# fpga.net
KiCad netlist of a schematic drawn in Altium Designer
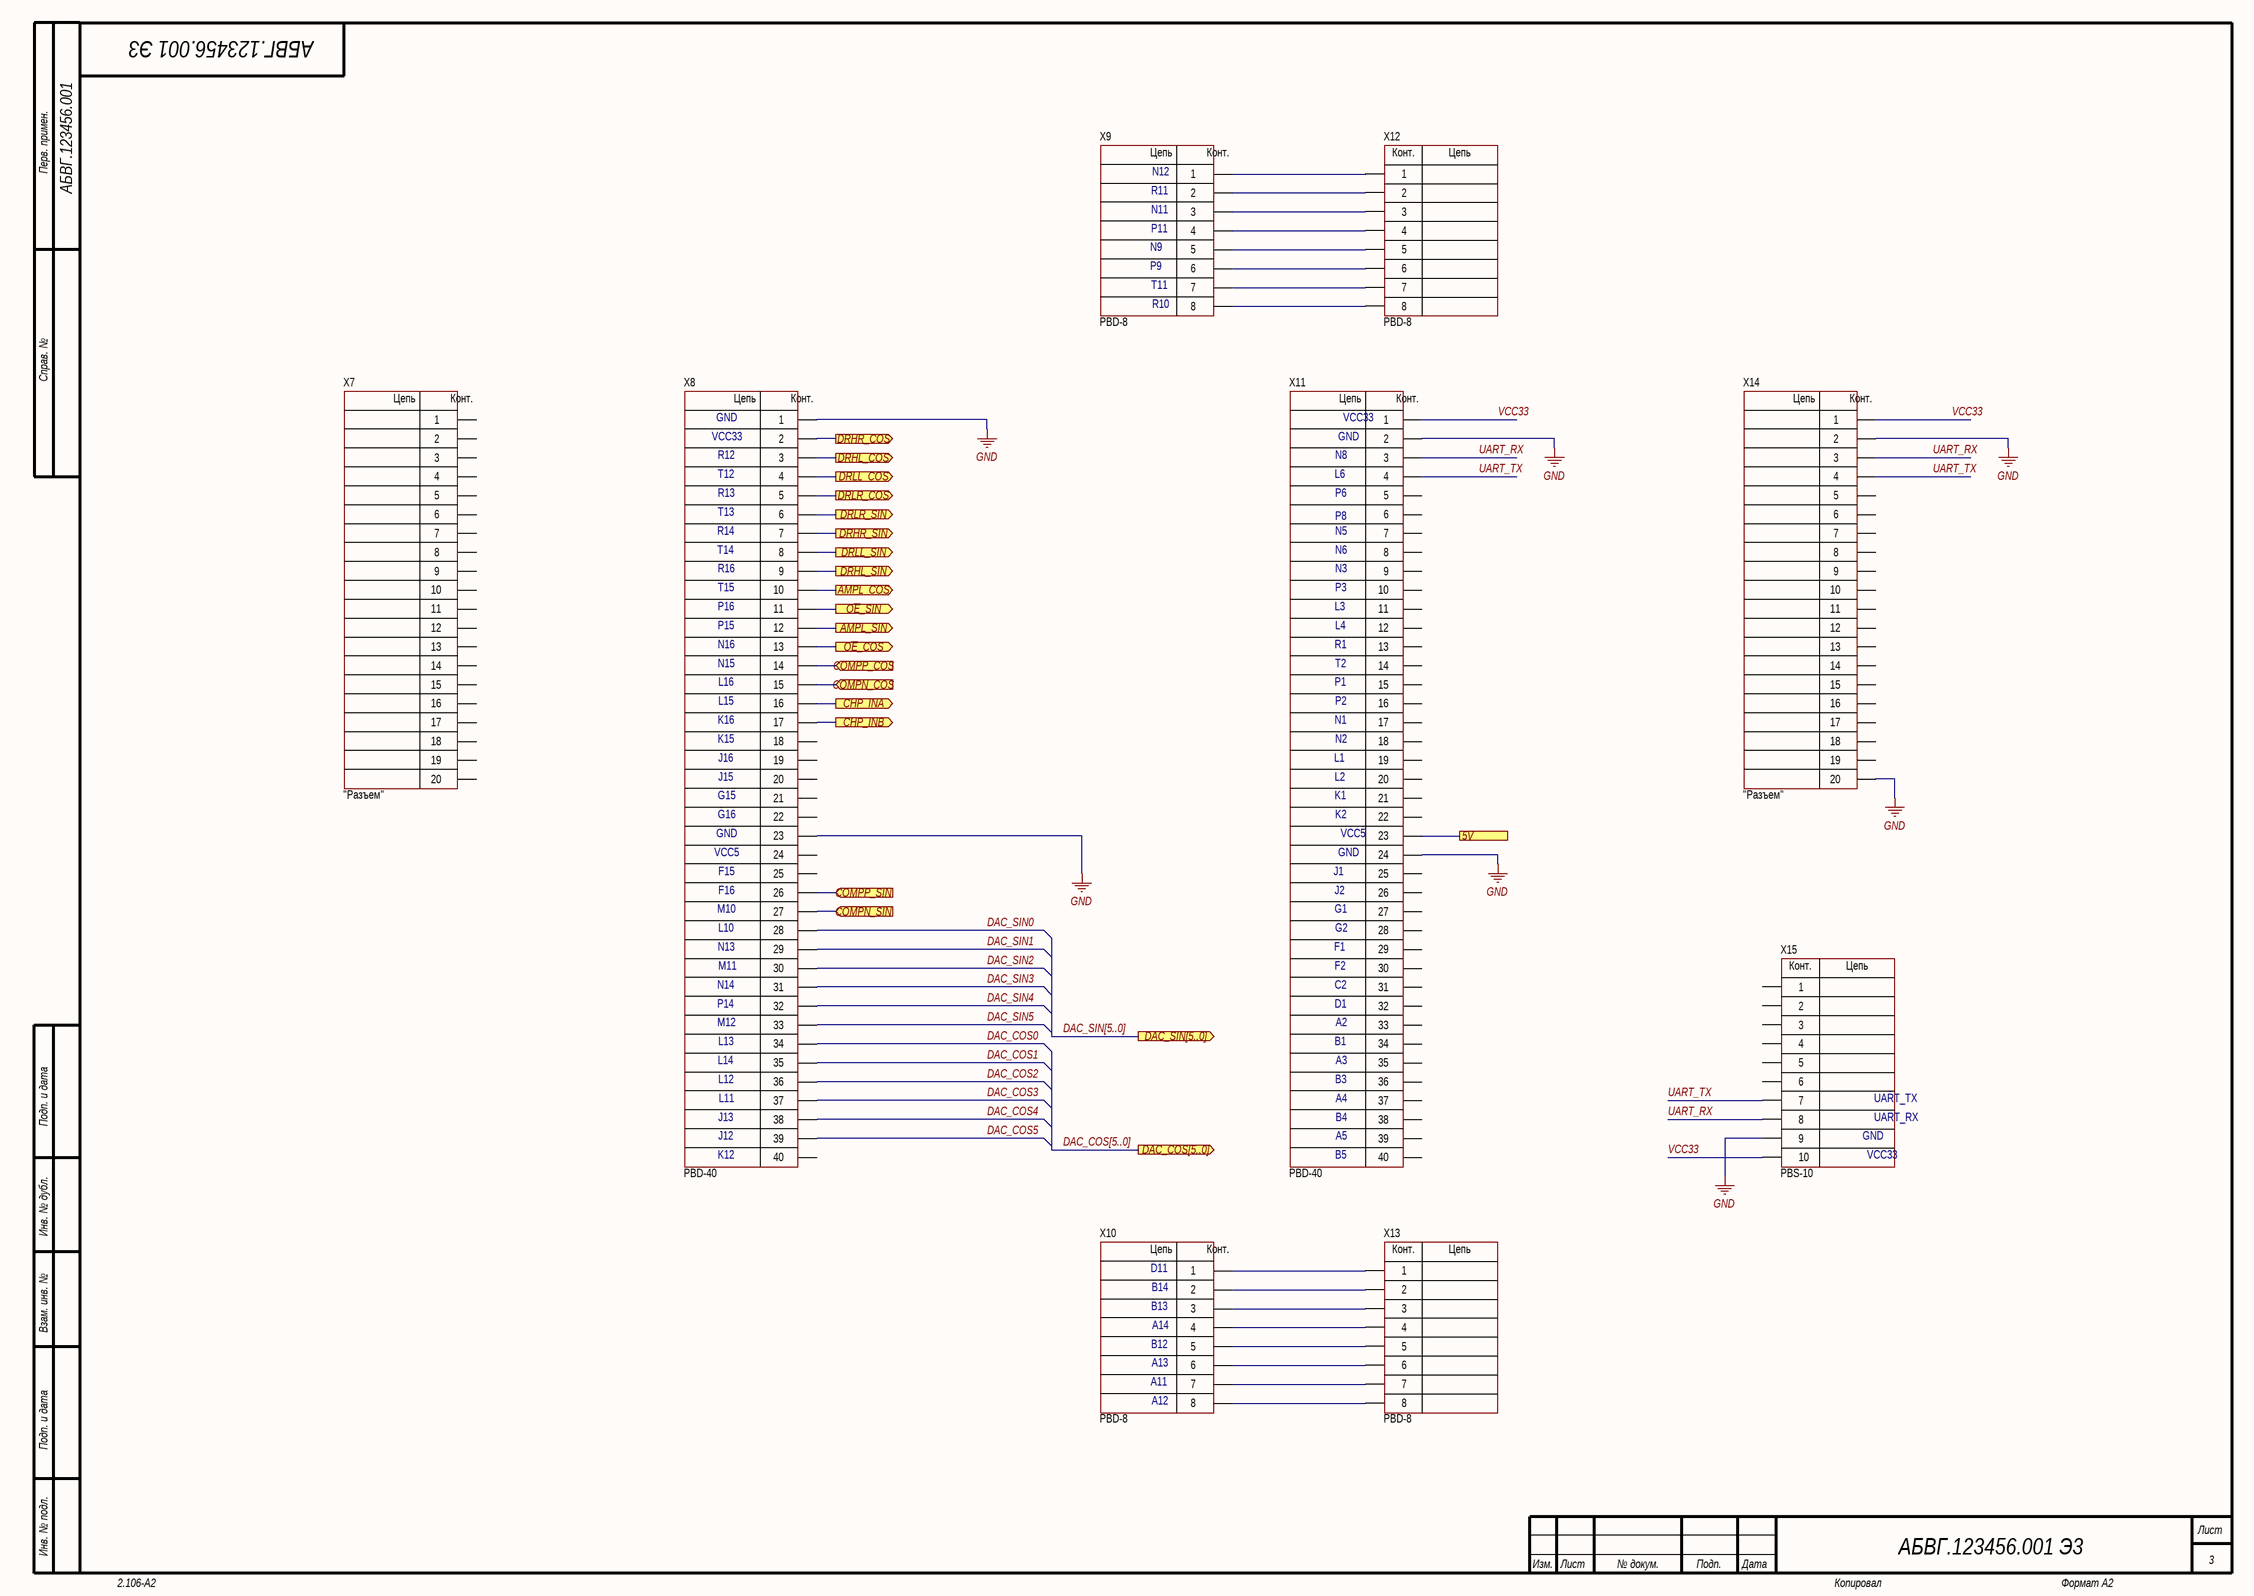
[diagram p0: fpga.SchDoc]

(export (version "E")
  (design (tool "Eeschema 10.0.6"))
  (components
    (comp (ref "X7")
      (value "~")
      (footprint "CON: PBD-20")
      (fields
        (field (name "MANUFACTURER") "Connfly")
        (field (name "VALUEMANUFACTURERPARTNUMBER") "Connector, 20pin, 2.54mm, 500VAC, 3A")
        (field (name "PARTNUMBER") "PBD-20")
        (field (name "COMMENTTEXT") "\"Разъем\"")
      )
      (libsource (lib "connector") (part "PBD-20"))
    )
    (comp (ref "X8")
      (value "~")
      (footprint "CON: PBD-40 (2.00)")
      (fields
        (field (name "MANUFACTURER") "Connfly")
        (field (name "VALUEMANUFACTURERPARTNUMBER") "Connector, 20pin, 2.54mm, 500VAC, 3A")
        (field (name "PARTNUMBER") "PBD-40")
      )
      (libsource (lib "connector") (part "PBD-40"))
    )
    (comp (ref "X9")
      (value "~")
      (footprint "CON: PBD2-8 (2.00)")
      (fields
        (field (name "MANUFACTURER") "Connfly")
        (field (name "VALUEMANUFACTURERPARTNUMBER") "Connector, 8pin, 2.54mm, 500VAC, 3A")
        (field (name "PARTNUMBER") "PBD-8")
      )
      (libsource (lib "connector") (part "PBD-8"))
    )
    (comp (ref "X10")
      (value "~")
      (footprint "CON: PBD2-8 (2.00)")
      (fields
        (field (name "MANUFACTURER") "Connfly")
        (field (name "VALUEMANUFACTURERPARTNUMBER") "Connector, 8pin, 2.54mm, 500VAC, 3A")
        (field (name "PARTNUMBER") "PBD-8")
      )
      (libsource (lib "connector") (part "PBD-8"))
    )
    (comp (ref "X11")
      (value "~")
      (footprint "CON: PBD-40 (2.00)")
      (fields
        (field (name "MANUFACTURER") "Connfly")
        (field (name "VALUEMANUFACTURERPARTNUMBER") "Connector, 20pin, 2.54mm, 500VAC, 3A")
        (field (name "PARTNUMBER") "PBD-40")
      )
      (libsource (lib "connector") (part "PBD-40"))
    )
    (comp (ref "X12")
      (value "~")
      (footprint "CON: PBD-8")
      (fields
        (field (name "MANUFACTURER") "Connfly")
        (field (name "VALUEMANUFACTURERPARTNUMBER") "Connector, 8pin, 2.54mm, 500VAC, 3A")
        (field (name "PARTNUMBER") "PBD-8")
      )
      (libsource (lib "") (part "PBD-8_1"))
    )
    (comp (ref "X13")
      (value "~")
      (footprint "CON: PBD-8")
      (fields
        (field (name "MANUFACTURER") "Connfly")
        (field (name "VALUEMANUFACTURERPARTNUMBER") "Connector, 8pin, 2.54mm, 500VAC, 3A")
        (field (name "PARTNUMBER") "PBD-8")
      )
      (libsource (lib "") (part "PBD-8_1"))
    )
    (comp (ref "X14")
      (value "~")
      (footprint "CON: PBD-20")
      (fields
        (field (name "MANUFACTURER") "Connfly")
        (field (name "VALUEMANUFACTURERPARTNUMBER") "Connector, 20pin, 2.54mm, 500VAC, 3A")
        (field (name "PARTNUMBER") "PBD-20")
        (field (name "COMMENTTEXT") "\"Разъем\"")
      )
      (libsource (lib "connector") (part "PBD-20"))
    )
    (comp (ref "X15")
      (value "~")
      (footprint "CON: PBS-10R")
      (fields
        (field (name "MANUFACTURER") "Connfly")
        (field (name "VALUEMANUFACTURERPARTNUMBER") "Connector, 10pin, 2.54mm, 500VAC, 3A")
        (field (name "PARTNUMBER") "PBS-10")
      )
      (libsource (lib "connector") (part "PBS-10R"))
    )
  )
  (nets
    (net (code "1") (name "/5V") (class "Default")
      (node (ref "X11") (pin "23") (pinfunction "23_23") (pintype "passive"))
    )
    (net (code "2") (name "/AMPL_COS") (class "Default")
      (node (ref "X8") (pin "10") (pinfunction "10_10") (pintype "passive"))
    )
    (net (code "3") (name "/AMPL_SIN") (class "Default")
      (node (ref "X8") (pin "12") (pinfunction "12_12") (pintype "passive"))
    )
    (net (code "4") (name "/CHP_INA") (class "Default")
      (node (ref "X8") (pin "16") (pinfunction "16_16") (pintype "passive"))
    )
    (net (code "5") (name "/CHP_INB") (class "Default")
      (node (ref "X8") (pin "17") (pinfunction "17_17") (pintype "passive"))
    )
    (net (code "6") (name "/COMPN_COS") (class "Default")
      (node (ref "X8") (pin "15") (pinfunction "15_15") (pintype "passive"))
    )
    (net (code "7") (name "/COMPN_SIN") (class "Default")
      (node (ref "X8") (pin "27") (pinfunction "27_27") (pintype "passive"))
    )
    (net (code "8") (name "/COMPP_COS") (class "Default")
      (node (ref "X8") (pin "14") (pinfunction "14_14") (pintype "passive"))
    )
    (net (code "9") (name "/COMPP_SIN") (class "Default")
      (node (ref "X8") (pin "26") (pinfunction "26_26") (pintype "passive"))
    )
    (net (code "10") (name "/DAC_COS0") (class "Default")
      (node (ref "X8") (pin "34") (pinfunction "34_34") (pintype "passive"))
    )
    (net (code "11") (name "/DAC_COS1") (class "Default")
      (node (ref "X8") (pin "35") (pinfunction "35_35") (pintype "passive"))
    )
    (net (code "12") (name "/DAC_COS2") (class "Default")
      (node (ref "X8") (pin "36") (pinfunction "36_36") (pintype "passive"))
    )
    (net (code "13") (name "/DAC_COS3") (class "Default")
      (node (ref "X8") (pin "37") (pinfunction "37_37") (pintype "passive"))
    )
    (net (code "14") (name "/DAC_COS4") (class "Default")
      (node (ref "X8") (pin "38") (pinfunction "38_38") (pintype "passive"))
    )
    (net (code "15") (name "/DAC_COS5") (class "Default")
      (node (ref "X8") (pin "39") (pinfunction "39_39") (pintype "passive"))
    )
    (net (code "17") (name "/DAC_SIN0") (class "Default")
      (node (ref "X8") (pin "28") (pinfunction "28_28") (pintype "passive"))
    )
    (net (code "18") (name "/DAC_SIN1") (class "Default")
      (node (ref "X8") (pin "29") (pinfunction "29_29") (pintype "passive"))
    )
    (net (code "19") (name "/DAC_SIN2") (class "Default")
      (node (ref "X8") (pin "30") (pinfunction "30_30") (pintype "passive"))
    )
    (net (code "20") (name "/DAC_SIN3") (class "Default")
      (node (ref "X8") (pin "31") (pinfunction "31_31") (pintype "passive"))
    )
    (net (code "21") (name "/DAC_SIN4") (class "Default")
      (node (ref "X8") (pin "32") (pinfunction "32_32") (pintype "passive"))
    )
    (net (code "22") (name "/DAC_SIN5") (class "Default")
      (node (ref "X8") (pin "33") (pinfunction "33_33") (pintype "passive"))
    )
    (net (code "24") (name "/DRHL_COS") (class "Default")
      (node (ref "X8") (pin "3") (pinfunction "3_3") (pintype "passive"))
    )
    (net (code "25") (name "/DRHL_SIN") (class "Default")
      (node (ref "X8") (pin "9") (pinfunction "9_9") (pintype "passive"))
    )
    (net (code "26") (name "/DRHR_COS") (class "Default")
      (node (ref "X8") (pin "2") (pinfunction "2_2") (pintype "passive"))
    )
    (net (code "27") (name "/DRHR_SIN") (class "Default")
      (node (ref "X8") (pin "7") (pinfunction "7_7") (pintype "passive"))
    )
    (net (code "28") (name "/DRLL_COS") (class "Default")
      (node (ref "X8") (pin "4") (pinfunction "4_4") (pintype "passive"))
    )
    (net (code "29") (name "/DRLL_SIN") (class "Default")
      (node (ref "X8") (pin "8") (pinfunction "8_8") (pintype "passive"))
    )
    (net (code "30") (name "/DRLR_COS") (class "Default")
      (node (ref "X8") (pin "5") (pinfunction "5_5") (pintype "passive"))
    )
    (net (code "31") (name "/DRLR_SIN") (class "Default")
      (node (ref "X8") (pin "6") (pinfunction "6_6") (pintype "passive"))
    )
    (net (code "32") (name "/O~{E}_COS") (class "Default")
      (node (ref "X8") (pin "13") (pinfunction "13_13") (pintype "passive"))
    )
    (net (code "33") (name "/O~{E}_SIN") (class "Default")
      (node (ref "X8") (pin "11") (pinfunction "11_11") (pintype "passive"))
    )
    (net (code "34") (name "/UART_RX") (class "Default")
      (node (ref "X11") (pin "3") (pinfunction "3_3") (pintype "passive"))
      (node (ref "X14") (pin "3") (pinfunction "3_3") (pintype "passive"))
      (node (ref "X15") (pin "8") (pinfunction "8_8") (pintype "power_in"))
    )
    (net (code "35") (name "/UART_TX") (class "Default")
      (node (ref "X11") (pin "4") (pinfunction "4_4") (pintype "passive"))
      (node (ref "X14") (pin "4") (pinfunction "4_4") (pintype "passive"))
      (node (ref "X15") (pin "7") (pinfunction "7_7") (pintype "power_in"))
    )
    (net (code "36") (name "/VCC33") (class "Default")
      (node (ref "X11") (pin "1") (pinfunction "1_1") (pintype "passive"))
      (node (ref "X14") (pin "1") (pinfunction "1_1") (pintype "passive"))
      (node (ref "X15") (pin "10") (pinfunction "10_10") (pintype "power_in"))
    )
    (net (code "37") (name "GND") (class "Default")
      (node (ref "X11") (pin "2") (pinfunction "2_2") (pintype "passive"))
      (node (ref "X11") (pin "24") (pinfunction "24_24") (pintype "passive"))
      (node (ref "X14") (pin "2") (pinfunction "2_2") (pintype "passive"))
      (node (ref "X14") (pin "20") (pinfunction "20_20") (pintype "passive"))
      (node (ref "X15") (pin "9") (pinfunction "9_9") (pintype "power_in"))
      (node (ref "X8") (pin "1") (pinfunction "1_1") (pintype "passive"))
      (node (ref "X8") (pin "23") (pinfunction "23_23") (pintype "passive"))
    )
    (net (code "38") (name "Net-(X10-Pad1)") (class "Default")
      (node (ref "X10") (pin "1") (pinfunction "1_1") (pintype "passive"))
      (node (ref "X13") (pin "1") (pinfunction "1_1") (pintype "passive"))
    )
    (net (code "39") (name "Net-(X10-Pad2)") (class "Default")
      (node (ref "X10") (pin "2") (pinfunction "2_2") (pintype "passive"))
      (node (ref "X13") (pin "2") (pinfunction "2_2") (pintype "passive"))
    )
    (net (code "40") (name "Net-(X10-Pad3)") (class "Default")
      (node (ref "X10") (pin "3") (pinfunction "3_3") (pintype "power_in"))
      (node (ref "X13") (pin "3") (pinfunction "3_3") (pintype "power_in"))
    )
    (net (code "41") (name "Net-(X10-Pad4)") (class "Default")
      (node (ref "X10") (pin "4") (pinfunction "4_4") (pintype "power_in"))
      (node (ref "X13") (pin "4") (pinfunction "4_4") (pintype "power_in"))
    )
    (net (code "42") (name "Net-(X10-Pad5)") (class "Default")
      (node (ref "X10") (pin "5") (pinfunction "5_5") (pintype "power_in"))
      (node (ref "X13") (pin "5") (pinfunction "5_5") (pintype "power_in"))
    )
    (net (code "43") (name "Net-(X10-Pad6)") (class "Default")
      (node (ref "X10") (pin "6") (pinfunction "6_6") (pintype "power_in"))
      (node (ref "X13") (pin "6") (pinfunction "6_6") (pintype "power_in"))
    )
    (net (code "44") (name "Net-(X10-Pad7)") (class "Default")
      (node (ref "X10") (pin "7") (pinfunction "7_7") (pintype "power_in"))
      (node (ref "X13") (pin "7") (pinfunction "7_7") (pintype "power_in"))
    )
    (net (code "45") (name "Net-(X10-Pad8)") (class "Default")
      (node (ref "X10") (pin "8") (pinfunction "8_8") (pintype "power_in"))
      (node (ref "X13") (pin "8") (pinfunction "8_8") (pintype "power_in"))
    )
    (net (code "46") (name "Net-(X12-Pad1)") (class "Default")
      (node (ref "X12") (pin "1") (pinfunction "1_1") (pintype "passive"))
      (node (ref "X9") (pin "1") (pinfunction "1_1") (pintype "passive"))
    )
    (net (code "47") (name "Net-(X12-Pad2)") (class "Default")
      (node (ref "X12") (pin "2") (pinfunction "2_2") (pintype "passive"))
      (node (ref "X9") (pin "2") (pinfunction "2_2") (pintype "passive"))
    )
    (net (code "48") (name "Net-(X12-Pad3)") (class "Default")
      (node (ref "X12") (pin "3") (pinfunction "3_3") (pintype "power_in"))
      (node (ref "X9") (pin "3") (pinfunction "3_3") (pintype "power_in"))
    )
    (net (code "49") (name "Net-(X12-Pad4)") (class "Default")
      (node (ref "X12") (pin "4") (pinfunction "4_4") (pintype "power_in"))
      (node (ref "X9") (pin "4") (pinfunction "4_4") (pintype "power_in"))
    )
    (net (code "50") (name "Net-(X12-Pad5)") (class "Default")
      (node (ref "X12") (pin "5") (pinfunction "5_5") (pintype "power_in"))
      (node (ref "X9") (pin "5") (pinfunction "5_5") (pintype "power_in"))
    )
    (net (code "51") (name "Net-(X12-Pad6)") (class "Default")
      (node (ref "X12") (pin "6") (pinfunction "6_6") (pintype "power_in"))
      (node (ref "X9") (pin "6") (pinfunction "6_6") (pintype "power_in"))
    )
    (net (code "52") (name "Net-(X12-Pad7)") (class "Default")
      (node (ref "X12") (pin "7") (pinfunction "7_7") (pintype "power_in"))
      (node (ref "X9") (pin "7") (pinfunction "7_7") (pintype "power_in"))
    )
    (net (code "53") (name "Net-(X12-Pad8)") (class "Default")
      (node (ref "X12") (pin "8") (pinfunction "8_8") (pintype "power_in"))
      (node (ref "X9") (pin "8") (pinfunction "8_8") (pintype "power_in"))
    )
    (net (code "54") (name "unconnected-(X7-Pad1)") (class "Default")
      (node (ref "X7") (pin "1") (pinfunction "1_1") (pintype "passive"))
    )
    (net (code "55") (name "unconnected-(X7-Pad2)") (class "Default")
      (node (ref "X7") (pin "2") (pinfunction "2_2") (pintype "passive"))
    )
    (net (code "56") (name "unconnected-(X7-Pad3)") (class "Default")
      (node (ref "X7") (pin "3") (pinfunction "3_3") (pintype "passive"))
    )
    (net (code "57") (name "unconnected-(X7-Pad4)") (class "Default")
      (node (ref "X7") (pin "4") (pinfunction "4_4") (pintype "passive"))
    )
    (net (code "58") (name "unconnected-(X7-Pad5)") (class "Default")
      (node (ref "X7") (pin "5") (pinfunction "5_5") (pintype "passive"))
    )
    (net (code "59") (name "unconnected-(X7-Pad6)") (class "Default")
      (node (ref "X7") (pin "6") (pinfunction "6_6") (pintype "passive"))
    )
    (net (code "60") (name "unconnected-(X7-Pad7)") (class "Default")
      (node (ref "X7") (pin "7") (pinfunction "7_7") (pintype "passive"))
    )
    (net (code "61") (name "unconnected-(X7-Pad8)") (class "Default")
      (node (ref "X7") (pin "8") (pinfunction "8_8") (pintype "passive"))
    )
    (net (code "62") (name "unconnected-(X7-Pad9)") (class "Default")
      (node (ref "X7") (pin "9") (pinfunction "9_9") (pintype "passive"))
    )
    (net (code "63") (name "unconnected-(X7-Pad10)") (class "Default")
      (node (ref "X7") (pin "10") (pinfunction "10_10") (pintype "passive"))
    )
    (net (code "64") (name "unconnected-(X7-Pad11)") (class "Default")
      (node (ref "X7") (pin "11") (pinfunction "11_11") (pintype "passive"))
    )
    (net (code "65") (name "unconnected-(X7-Pad12)") (class "Default")
      (node (ref "X7") (pin "12") (pinfunction "12_12") (pintype "passive"))
    )
    (net (code "66") (name "unconnected-(X7-Pad13)") (class "Default")
      (node (ref "X7") (pin "13") (pinfunction "13_13") (pintype "passive"))
    )
    (net (code "67") (name "unconnected-(X7-Pad14)") (class "Default")
      (node (ref "X7") (pin "14") (pinfunction "14_14") (pintype "passive"))
    )
    (net (code "68") (name "unconnected-(X7-Pad15)") (class "Default")
      (node (ref "X7") (pin "15") (pinfunction "15_15") (pintype "passive"))
    )
    (net (code "69") (name "unconnected-(X7-Pad16)") (class "Default")
      (node (ref "X7") (pin "16") (pinfunction "16_16") (pintype "passive"))
    )
    (net (code "70") (name "unconnected-(X7-Pad17)") (class "Default")
      (node (ref "X7") (pin "17") (pinfunction "17_17") (pintype "passive"))
    )
    (net (code "71") (name "unconnected-(X7-Pad18)") (class "Default")
      (node (ref "X7") (pin "18") (pinfunction "18_18") (pintype "passive"))
    )
    (net (code "72") (name "unconnected-(X7-Pad19)") (class "Default")
      (node (ref "X7") (pin "19") (pinfunction "19_19") (pintype "passive"))
    )
    (net (code "73") (name "unconnected-(X7-Pad20)") (class "Default")
      (node (ref "X7") (pin "20") (pinfunction "20_20") (pintype "passive"))
    )
    (net (code "74") (name "unconnected-(X8-Pad18)") (class "Default")
      (node (ref "X8") (pin "18") (pinfunction "18_18") (pintype "passive"))
    )
    (net (code "75") (name "unconnected-(X8-Pad19)") (class "Default")
      (node (ref "X8") (pin "19") (pinfunction "19_19") (pintype "passive"))
    )
    (net (code "76") (name "unconnected-(X8-Pad20)") (class "Default")
      (node (ref "X8") (pin "20") (pinfunction "20_20") (pintype "passive"))
    )
    (net (code "77") (name "unconnected-(X8-Pad21)") (class "Default")
      (node (ref "X8") (pin "21") (pinfunction "21_21") (pintype "passive"))
    )
    (net (code "78") (name "unconnected-(X8-Pad22)") (class "Default")
      (node (ref "X8") (pin "22") (pinfunction "22_22") (pintype "passive"))
    )
    (net (code "79") (name "unconnected-(X8-Pad24)") (class "Default")
      (node (ref "X8") (pin "24") (pinfunction "24_24") (pintype "passive"))
    )
    (net (code "80") (name "unconnected-(X8-Pad25)") (class "Default")
      (node (ref "X8") (pin "25") (pinfunction "25_25") (pintype "passive"))
    )
    (net (code "81") (name "unconnected-(X8-Pad40)") (class "Default")
      (node (ref "X8") (pin "40") (pinfunction "40_40") (pintype "passive"))
    )
    (net (code "82") (name "unconnected-(X11-Pad5)") (class "Default")
      (node (ref "X11") (pin "5") (pinfunction "5_5") (pintype "passive"))
    )
    (net (code "83") (name "unconnected-(X11-Pad6)") (class "Default")
      (node (ref "X11") (pin "6") (pinfunction "6_6") (pintype "passive"))
    )
    (net (code "84") (name "unconnected-(X11-Pad7)") (class "Default")
      (node (ref "X11") (pin "7") (pinfunction "7_7") (pintype "passive"))
    )
    (net (code "85") (name "unconnected-(X11-Pad8)") (class "Default")
      (node (ref "X11") (pin "8") (pinfunction "8_8") (pintype "passive"))
    )
    (net (code "86") (name "unconnected-(X11-Pad9)") (class "Default")
      (node (ref "X11") (pin "9") (pinfunction "9_9") (pintype "passive"))
    )
    (net (code "87") (name "unconnected-(X11-Pad10)") (class "Default")
      (node (ref "X11") (pin "10") (pinfunction "10_10") (pintype "passive"))
    )
    (net (code "88") (name "unconnected-(X11-Pad11)") (class "Default")
      (node (ref "X11") (pin "11") (pinfunction "11_11") (pintype "passive"))
    )
    (net (code "89") (name "unconnected-(X11-Pad12)") (class "Default")
      (node (ref "X11") (pin "12") (pinfunction "12_12") (pintype "passive"))
    )
    (net (code "90") (name "unconnected-(X11-Pad13)") (class "Default")
      (node (ref "X11") (pin "13") (pinfunction "13_13") (pintype "passive"))
    )
    (net (code "91") (name "unconnected-(X11-Pad14)") (class "Default")
      (node (ref "X11") (pin "14") (pinfunction "14_14") (pintype "passive"))
    )
    (net (code "92") (name "unconnected-(X11-Pad15)") (class "Default")
      (node (ref "X11") (pin "15") (pinfunction "15_15") (pintype "passive"))
    )
    (net (code "93") (name "unconnected-(X11-Pad16)") (class "Default")
      (node (ref "X11") (pin "16") (pinfunction "16_16") (pintype "passive"))
    )
    (net (code "94") (name "unconnected-(X11-Pad17)") (class "Default")
      (node (ref "X11") (pin "17") (pinfunction "17_17") (pintype "passive"))
    )
    (net (code "95") (name "unconnected-(X11-Pad18)") (class "Default")
      (node (ref "X11") (pin "18") (pinfunction "18_18") (pintype "passive"))
    )
    (net (code "96") (name "unconnected-(X11-Pad19)") (class "Default")
      (node (ref "X11") (pin "19") (pinfunction "19_19") (pintype "passive"))
    )
    (net (code "97") (name "unconnected-(X11-Pad20)") (class "Default")
      (node (ref "X11") (pin "20") (pinfunction "20_20") (pintype "passive"))
    )
    (net (code "98") (name "unconnected-(X11-Pad21)") (class "Default")
      (node (ref "X11") (pin "21") (pinfunction "21_21") (pintype "passive"))
    )
    (net (code "99") (name "unconnected-(X11-Pad22)") (class "Default")
      (node (ref "X11") (pin "22") (pinfunction "22_22") (pintype "passive"))
    )
    (net (code "100") (name "unconnected-(X11-Pad25)") (class "Default")
      (node (ref "X11") (pin "25") (pinfunction "25_25") (pintype "passive"))
    )
    (net (code "101") (name "unconnected-(X11-Pad26)") (class "Default")
      (node (ref "X11") (pin "26") (pinfunction "26_26") (pintype "passive"))
    )
    (net (code "102") (name "unconnected-(X11-Pad27)") (class "Default")
      (node (ref "X11") (pin "27") (pinfunction "27_27") (pintype "passive"))
    )
    (net (code "103") (name "unconnected-(X11-Pad28)") (class "Default")
      (node (ref "X11") (pin "28") (pinfunction "28_28") (pintype "passive"))
    )
    (net (code "104") (name "unconnected-(X11-Pad29)") (class "Default")
      (node (ref "X11") (pin "29") (pinfunction "29_29") (pintype "passive"))
    )
    (net (code "105") (name "unconnected-(X11-Pad30)") (class "Default")
      (node (ref "X11") (pin "30") (pinfunction "30_30") (pintype "passive"))
    )
    (net (code "106") (name "unconnected-(X11-Pad31)") (class "Default")
      (node (ref "X11") (pin "31") (pinfunction "31_31") (pintype "passive"))
    )
    (net (code "107") (name "unconnected-(X11-Pad32)") (class "Default")
      (node (ref "X11") (pin "32") (pinfunction "32_32") (pintype "passive"))
    )
    (net (code "108") (name "unconnected-(X11-Pad33)") (class "Default")
      (node (ref "X11") (pin "33") (pinfunction "33_33") (pintype "passive"))
    )
    (net (code "109") (name "unconnected-(X11-Pad34)") (class "Default")
      (node (ref "X11") (pin "34") (pinfunction "34_34") (pintype "passive"))
    )
    (net (code "110") (name "unconnected-(X11-Pad35)") (class "Default")
      (node (ref "X11") (pin "35") (pinfunction "35_35") (pintype "passive"))
    )
    (net (code "111") (name "unconnected-(X11-Pad36)") (class "Default")
      (node (ref "X11") (pin "36") (pinfunction "36_36") (pintype "passive"))
    )
    (net (code "112") (name "unconnected-(X11-Pad37)") (class "Default")
      (node (ref "X11") (pin "37") (pinfunction "37_37") (pintype "passive"))
    )
    (net (code "113") (name "unconnected-(X11-Pad38)") (class "Default")
      (node (ref "X11") (pin "38") (pinfunction "38_38") (pintype "passive"))
    )
    (net (code "114") (name "unconnected-(X11-Pad39)") (class "Default")
      (node (ref "X11") (pin "39") (pinfunction "39_39") (pintype "passive"))
    )
    (net (code "115") (name "unconnected-(X11-Pad40)") (class "Default")
      (node (ref "X11") (pin "40") (pinfunction "40_40") (pintype "passive"))
    )
    (net (code "116") (name "unconnected-(X14-Pad5)") (class "Default")
      (node (ref "X14") (pin "5") (pinfunction "5_5") (pintype "passive"))
    )
    (net (code "117") (name "unconnected-(X14-Pad6)") (class "Default")
      (node (ref "X14") (pin "6") (pinfunction "6_6") (pintype "passive"))
    )
    (net (code "118") (name "unconnected-(X14-Pad7)") (class "Default")
      (node (ref "X14") (pin "7") (pinfunction "7_7") (pintype "passive"))
    )
    (net (code "119") (name "unconnected-(X14-Pad8)") (class "Default")
      (node (ref "X14") (pin "8") (pinfunction "8_8") (pintype "passive"))
    )
    (net (code "120") (name "unconnected-(X14-Pad9)") (class "Default")
      (node (ref "X14") (pin "9") (pinfunction "9_9") (pintype "passive"))
    )
    (net (code "121") (name "unconnected-(X14-Pad10)") (class "Default")
      (node (ref "X14") (pin "10") (pinfunction "10_10") (pintype "passive"))
    )
    (net (code "122") (name "unconnected-(X14-Pad11)") (class "Default")
      (node (ref "X14") (pin "11") (pinfunction "11_11") (pintype "passive"))
    )
    (net (code "123") (name "unconnected-(X14-Pad12)") (class "Default")
      (node (ref "X14") (pin "12") (pinfunction "12_12") (pintype "passive"))
    )
    (net (code "124") (name "unconnected-(X14-Pad13)") (class "Default")
      (node (ref "X14") (pin "13") (pinfunction "13_13") (pintype "passive"))
    )
    (net (code "125") (name "unconnected-(X14-Pad14)") (class "Default")
      (node (ref "X14") (pin "14") (pinfunction "14_14") (pintype "passive"))
    )
    (net (code "126") (name "unconnected-(X14-Pad15)") (class "Default")
      (node (ref "X14") (pin "15") (pinfunction "15_15") (pintype "passive"))
    )
    (net (code "127") (name "unconnected-(X14-Pad16)") (class "Default")
      (node (ref "X14") (pin "16") (pinfunction "16_16") (pintype "passive"))
    )
    (net (code "128") (name "unconnected-(X14-Pad17)") (class "Default")
      (node (ref "X14") (pin "17") (pinfunction "17_17") (pintype "passive"))
    )
    (net (code "129") (name "unconnected-(X14-Pad18)") (class "Default")
      (node (ref "X14") (pin "18") (pinfunction "18_18") (pintype "passive"))
    )
    (net (code "130") (name "unconnected-(X14-Pad19)") (class "Default")
      (node (ref "X14") (pin "19") (pinfunction "19_19") (pintype "passive"))
    )
    (net (code "131") (name "unconnected-(X15-Pad1)") (class "Default")
      (node (ref "X15") (pin "1") (pinfunction "1_1") (pintype "passive"))
    )
    (net (code "132") (name "unconnected-(X15-Pad2)") (class "Default")
      (node (ref "X15") (pin "2") (pinfunction "2_2") (pintype "passive"))
    )
    (net (code "133") (name "unconnected-(X15-Pad3)") (class "Default")
      (node (ref "X15") (pin "3") (pinfunction "3_3") (pintype "power_in"))
    )
    (net (code "134") (name "unconnected-(X15-Pad4)") (class "Default")
      (node (ref "X15") (pin "4") (pinfunction "4_4") (pintype "power_in"))
    )
    (net (code "135") (name "unconnected-(X15-Pad5)") (class "Default")
      (node (ref "X15") (pin "5") (pinfunction "5_5") (pintype "power_in"))
    )
    (net (code "136") (name "unconnected-(X15-Pad6)") (class "Default")
      (node (ref "X15") (pin "6") (pinfunction "6_6") (pintype "power_in"))
    )
  )
)
